# PowerSupply.net
KiCad netlist of a schematic drawn in Altium Designer
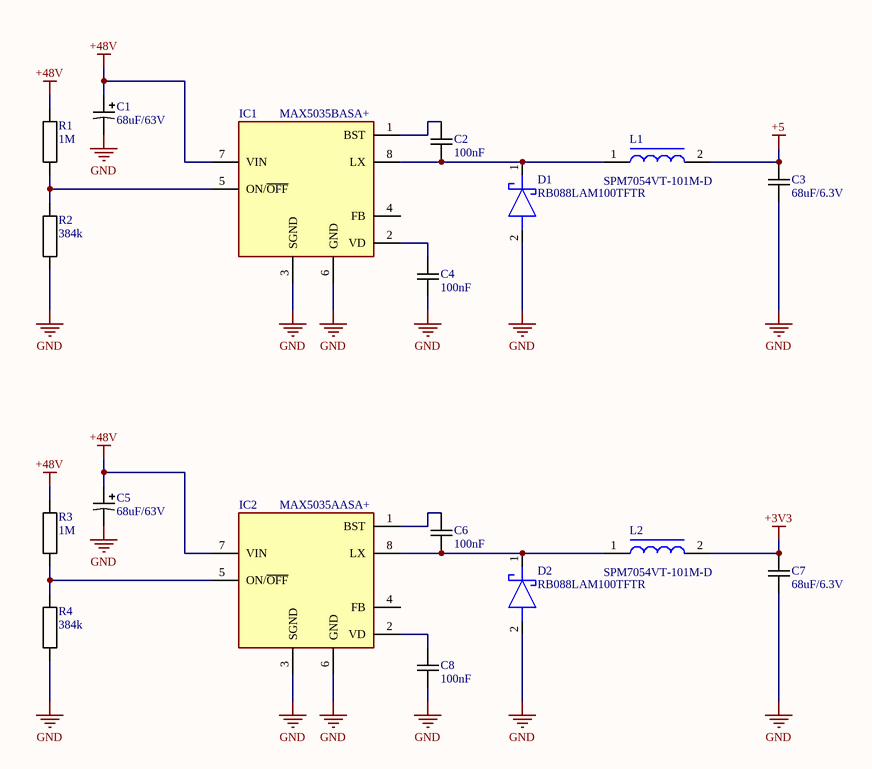
[diagram p0: PowerSupply.SchDoc]

(export (version "E")
  (design (tool "Eeschema 10.0.6"))
  (components
    (comp (ref "C1")
      (value "68uF/63V")
      (footprint "Capacitor POL SMD D10.0 H10.0")
      (description "Capacitor polarized")
      (libsource (lib "Capacitor") (part "Capacitor Polarized"))
    )
    (comp (ref "C2")
      (value "100nF")
      (footprint "CAPACITOR 1608 REFLOW")
      (description "Capacitor")
      (libsource (lib "Capacitor") (part "Capacitor"))
    )
    (comp (ref "C3")
      (value "68uF/6.3V")
      (footprint "CAPACITOR 2012 REFLOW")
      (description "Capacitor")
      (libsource (lib "Capacitor") (part "Capacitor"))
    )
    (comp (ref "C4")
      (value "100nF")
      (footprint "CAPACITOR 1608 REFLOW")
      (description "Capacitor")
      (libsource (lib "Capacitor") (part "Capacitor"))
    )
    (comp (ref "C5")
      (value "68uF/63V")
      (footprint "Capacitor POL SMD D10.0 H10.0")
      (description "Capacitor polarized")
      (libsource (lib "Capacitor") (part "Capacitor Polarized"))
    )
    (comp (ref "C6")
      (value "100nF")
      (footprint "CAPACITOR 1608 REFLOW")
      (description "Capacitor")
      (libsource (lib "Capacitor") (part "Capacitor"))
    )
    (comp (ref "C7")
      (value "68uF/6.3V")
      (footprint "CAPACITOR 2012 REFLOW")
      (description "Capacitor")
      (libsource (lib "Capacitor") (part "Capacitor"))
    )
    (comp (ref "C8")
      (value "100nF")
      (footprint "CAPACITOR 1608 REFLOW")
      (description "Capacitor")
      (libsource (lib "Capacitor") (part "Capacitor"))
    )
    (comp (ref "D1")
      (value "RB088LAM100TFTR")
      (footprint "SamacSys:SODFL4725X105N")
      (description "Schottky Diode")
      (fields (field (name "MOUSER PART NUMBER") "755-RB088LAM100TFTR"))
      (libsource (lib "*") (part "RB088LAM100TFTR"))
    )
    (comp (ref "D2")
      (value "RB088LAM100TFTR")
      (footprint "SamacSys:SODFL4725X105N")
      (description "Schottky Diode")
      (fields (field (name "MOUSER PART NUMBER") "755-RB088LAM100TFTR"))
      (libsource (lib "*") (part "RB088LAM100TFTR"))
    )
    (comp (ref "IC1")
      (value "MAX5035BASA+")
      (footprint "SamacSys:SOIC127P600X175-8N")
      (description "Integrated Circuit")
      (fields (field (name "MOUSER PART NUMBER") "700-MAX5035BASA"))
      (libsource (lib "SamacSys") (part "MAX5035BASA+"))
    )
    (comp (ref "IC2")
      (value "MAX5035AASA+")
      (footprint "SamacSys:SOIC127P600X175-8N")
      (description "Integrated Circuit")
      (fields
        (field (name "MANUFACTURER_PART_NUMBER") "MAX5035BASA+")
        (field (name "MOUSER PART NUMBER") "700-MAX5035BASA")
      )
      (libsource (lib "SamacSys") (part "MAX5035BASA+"))
    )
    (comp (ref "L1")
      (value "SPM7054VT-101M-D")
      (footprint "SamacSys:SPM7054VT")
      (description "Inductor (FeSi Core)")
      (fields (field (name "MOUSER PART NUMBER") "810-SPM7054VT-101M-D"))
      (libsource (lib "*") (part "SPM7054VT-101M-D"))
    )
    (comp (ref "L2")
      (value "SPM7054VT-101M-D")
      (footprint "SamacSys:SPM7054VT")
      (description "Inductor (FeSi Core)")
      (fields (field (name "MOUSER PART NUMBER") "810-SPM7054VT-101M-D"))
      (libsource (lib "*") (part "SPM7054VT-101M-D"))
    )
    (comp (ref "R1")
      (value "1M")
      (footprint "RESISTOR 1608 REFLOW")
      (description "Resistor")
      (libsource (lib "Resistor") (part "Resistor"))
    )
    (comp (ref "R2")
      (value "384k")
      (footprint "RESISTOR 1608 REFLOW")
      (description "Resistor")
      (libsource (lib "Resistor") (part "Resistor"))
    )
    (comp (ref "R3")
      (value "1M")
      (footprint "RESISTOR 1608 REFLOW")
      (description "Resistor")
      (libsource (lib "Resistor") (part "Resistor"))
    )
    (comp (ref "R4")
      (value "384k")
      (footprint "RESISTOR 1608 REFLOW")
      (description "Resistor")
      (libsource (lib "Resistor") (part "Resistor"))
    )
  )
  (nets
    (net (code "1") (name "+3V3") (class "Default")
      (node (ref "C7") (pin "2") (pinfunction "2_2") (pintype "passive"))
      (node (ref "L2") (pin "2") (pinfunction "2_2") (pintype "passive"))
    )
    (net (code "2") (name "+5") (class "Default")
      (node (ref "C3") (pin "2") (pinfunction "2_2") (pintype "passive"))
      (node (ref "L1") (pin "2") (pinfunction "2_2") (pintype "passive"))
    )
    (net (code "3") (name "+48V") (class "Default")
      (node (ref "C1") (pin "1") (pinfunction "1_1") (pintype "passive"))
      (node (ref "C5") (pin "1") (pinfunction "1_1") (pintype "passive"))
      (node (ref "IC1") (pin "7") (pinfunction "VIN_7") (pintype "passive"))
      (node (ref "IC2") (pin "7") (pinfunction "VIN_7") (pintype "passive"))
      (node (ref "R1") (pin "2") (pinfunction "2_2") (pintype "passive"))
      (node (ref "R3") (pin "2") (pinfunction "2_2") (pintype "passive"))
    )
    (net (code "4") (name "GND") (class "Default")
      (node (ref "C1") (pin "2") (pinfunction "2_2") (pintype "passive"))
      (node (ref "C3") (pin "1") (pinfunction "1_1") (pintype "passive"))
      (node (ref "C4") (pin "2") (pinfunction "2_2") (pintype "passive"))
      (node (ref "C5") (pin "2") (pinfunction "2_2") (pintype "passive"))
      (node (ref "C7") (pin "1") (pinfunction "1_1") (pintype "passive"))
      (node (ref "C8") (pin "2") (pinfunction "2_2") (pintype "passive"))
      (node (ref "D1") (pin "2") (pinfunction "A_2") (pintype "passive"))
      (node (ref "D2") (pin "2") (pinfunction "A_2") (pintype "passive"))
      (node (ref "IC1") (pin "3") (pinfunction "SGND_3") (pintype "passive"))
      (node (ref "IC1") (pin "6") (pinfunction "GND_6") (pintype "passive"))
      (node (ref "IC2") (pin "3") (pinfunction "SGND_3") (pintype "passive"))
      (node (ref "IC2") (pin "6") (pinfunction "GND_6") (pintype "passive"))
      (node (ref "R2") (pin "1") (pinfunction "1_1") (pintype "passive"))
      (node (ref "R4") (pin "1") (pinfunction "1_1") (pintype "passive"))
    )
    (net (code "5") (name "Net-(D1-K)") (class "Default")
      (node (ref "C2") (pin "2") (pinfunction "2_2") (pintype "passive"))
      (node (ref "D1") (pin "1") (pinfunction "K_1") (pintype "passive"))
      (node (ref "IC1") (pin "8") (pinfunction "LX_8") (pintype "passive"))
      (node (ref "L1") (pin "1") (pinfunction "1_1") (pintype "passive"))
    )
    (net (code "6") (name "Net-(D2-K)") (class "Default")
      (node (ref "C6") (pin "2") (pinfunction "2_2") (pintype "passive"))
      (node (ref "D2") (pin "1") (pinfunction "K_1") (pintype "passive"))
      (node (ref "IC2") (pin "8") (pinfunction "LX_8") (pintype "passive"))
      (node (ref "L2") (pin "1") (pinfunction "1_1") (pintype "passive"))
    )
    (net (code "7") (name "Net-(IC1-BST)") (class "Default")
      (node (ref "C2") (pin "1") (pinfunction "1_1") (pintype "passive"))
      (node (ref "IC1") (pin "1") (pinfunction "BST_1") (pintype "passive"))
    )
    (net (code "8") (name "Net-(IC1-ON{slash}~{OFF})") (class "Default")
      (node (ref "IC1") (pin "5") (pinfunction "ON/~{OFF}_5") (pintype "passive"))
      (node (ref "R1") (pin "1") (pinfunction "1_1") (pintype "passive"))
      (node (ref "R2") (pin "2") (pinfunction "2_2") (pintype "passive"))
    )
    (net (code "9") (name "Net-(IC1-VD)") (class "Default")
      (node (ref "C4") (pin "1") (pinfunction "1_1") (pintype "passive"))
      (node (ref "IC1") (pin "2") (pinfunction "VD_2") (pintype "passive"))
    )
    (net (code "10") (name "Net-(IC2-BST)") (class "Default")
      (node (ref "C6") (pin "1") (pinfunction "1_1") (pintype "passive"))
      (node (ref "IC2") (pin "1") (pinfunction "BST_1") (pintype "passive"))
    )
    (net (code "11") (name "Net-(IC2-ON{slash}~{OFF})") (class "Default")
      (node (ref "IC2") (pin "5") (pinfunction "ON/~{OFF}_5") (pintype "passive"))
      (node (ref "R3") (pin "1") (pinfunction "1_1") (pintype "passive"))
      (node (ref "R4") (pin "2") (pinfunction "2_2") (pintype "passive"))
    )
    (net (code "12") (name "Net-(IC2-VD)") (class "Default")
      (node (ref "C8") (pin "1") (pinfunction "1_1") (pintype "passive"))
      (node (ref "IC2") (pin "2") (pinfunction "VD_2") (pintype "passive"))
    )
    (net (code "13") (name "unconnected-(IC1-FB-Pad4)") (class "Default")
      (node (ref "IC1") (pin "4") (pinfunction "FB_4") (pintype "passive"))
    )
    (net (code "14") (name "unconnected-(IC2-FB-Pad4)") (class "Default")
      (node (ref "IC2") (pin "4") (pinfunction "FB_4") (pintype "passive"))
    )
  )
)
